# blinky.net
KiCad netlist of a schematic drawn in EAGLE
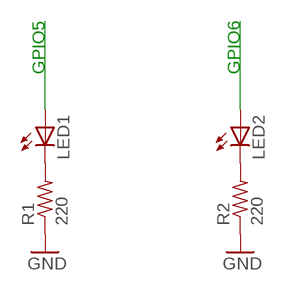
[diagram p0: schematic, sheet 1]

(export (version "E")
  (design (tool "Eeschema 10.0.6"))
  (components
    (comp (ref "LED1")
      (value "LED5MM")
      (footprint "eagle-import:LED5MM")
      (libsource (lib "eagle-import") (part "LED5MM"))
    )
    (comp (ref "LED2")
      (value "LED5MM")
      (footprint "eagle-import:LED5MM")
      (libsource (lib "eagle-import") (part "LED5MM"))
    )
    (comp (ref "R1")
      (value "220")
      (footprint "eagle-import:R0603")
      (libsource (lib "eagle-import") (part "R-US_R0603"))
    )
    (comp (ref "R2")
      (value "220")
      (footprint "eagle-import:R0603")
      (libsource (lib "eagle-import") (part "R-US_R0603"))
    )
  )
  (nets
    (net (code "1") (name "GND") (class "Default")
      (node (ref "R1") (pin "1") (pinfunction "1_1") (pintype "passive"))
      (node (ref "R2") (pin "1") (pinfunction "1_1") (pintype "passive"))
    )
    (net (code "2") (name "Net-(LED1-C)") (class "Default")
      (node (ref "LED1") (pin "K") (pinfunction "C_K") (pintype "passive"))
      (node (ref "R1") (pin "2") (pinfunction "2_2") (pintype "passive"))
    )
    (net (code "3") (name "Net-(LED2-C)") (class "Default")
      (node (ref "LED2") (pin "K") (pinfunction "C_K") (pintype "passive"))
      (node (ref "R2") (pin "2") (pinfunction "2_2") (pintype "passive"))
    )
    (net (code "4") (name "unconnected-(LED1-PadA)") (class "Default")
      (node (ref "LED1") (pin "A") (pinfunction "A_A") (pintype "passive"))
    )
    (net (code "5") (name "unconnected-(LED2-PadA)") (class "Default")
      (node (ref "LED2") (pin "A") (pinfunction "A_A") (pintype "passive"))
    )
  )
)
